# S05.net
KiCad netlist of a schematic drawn in Altium Designer
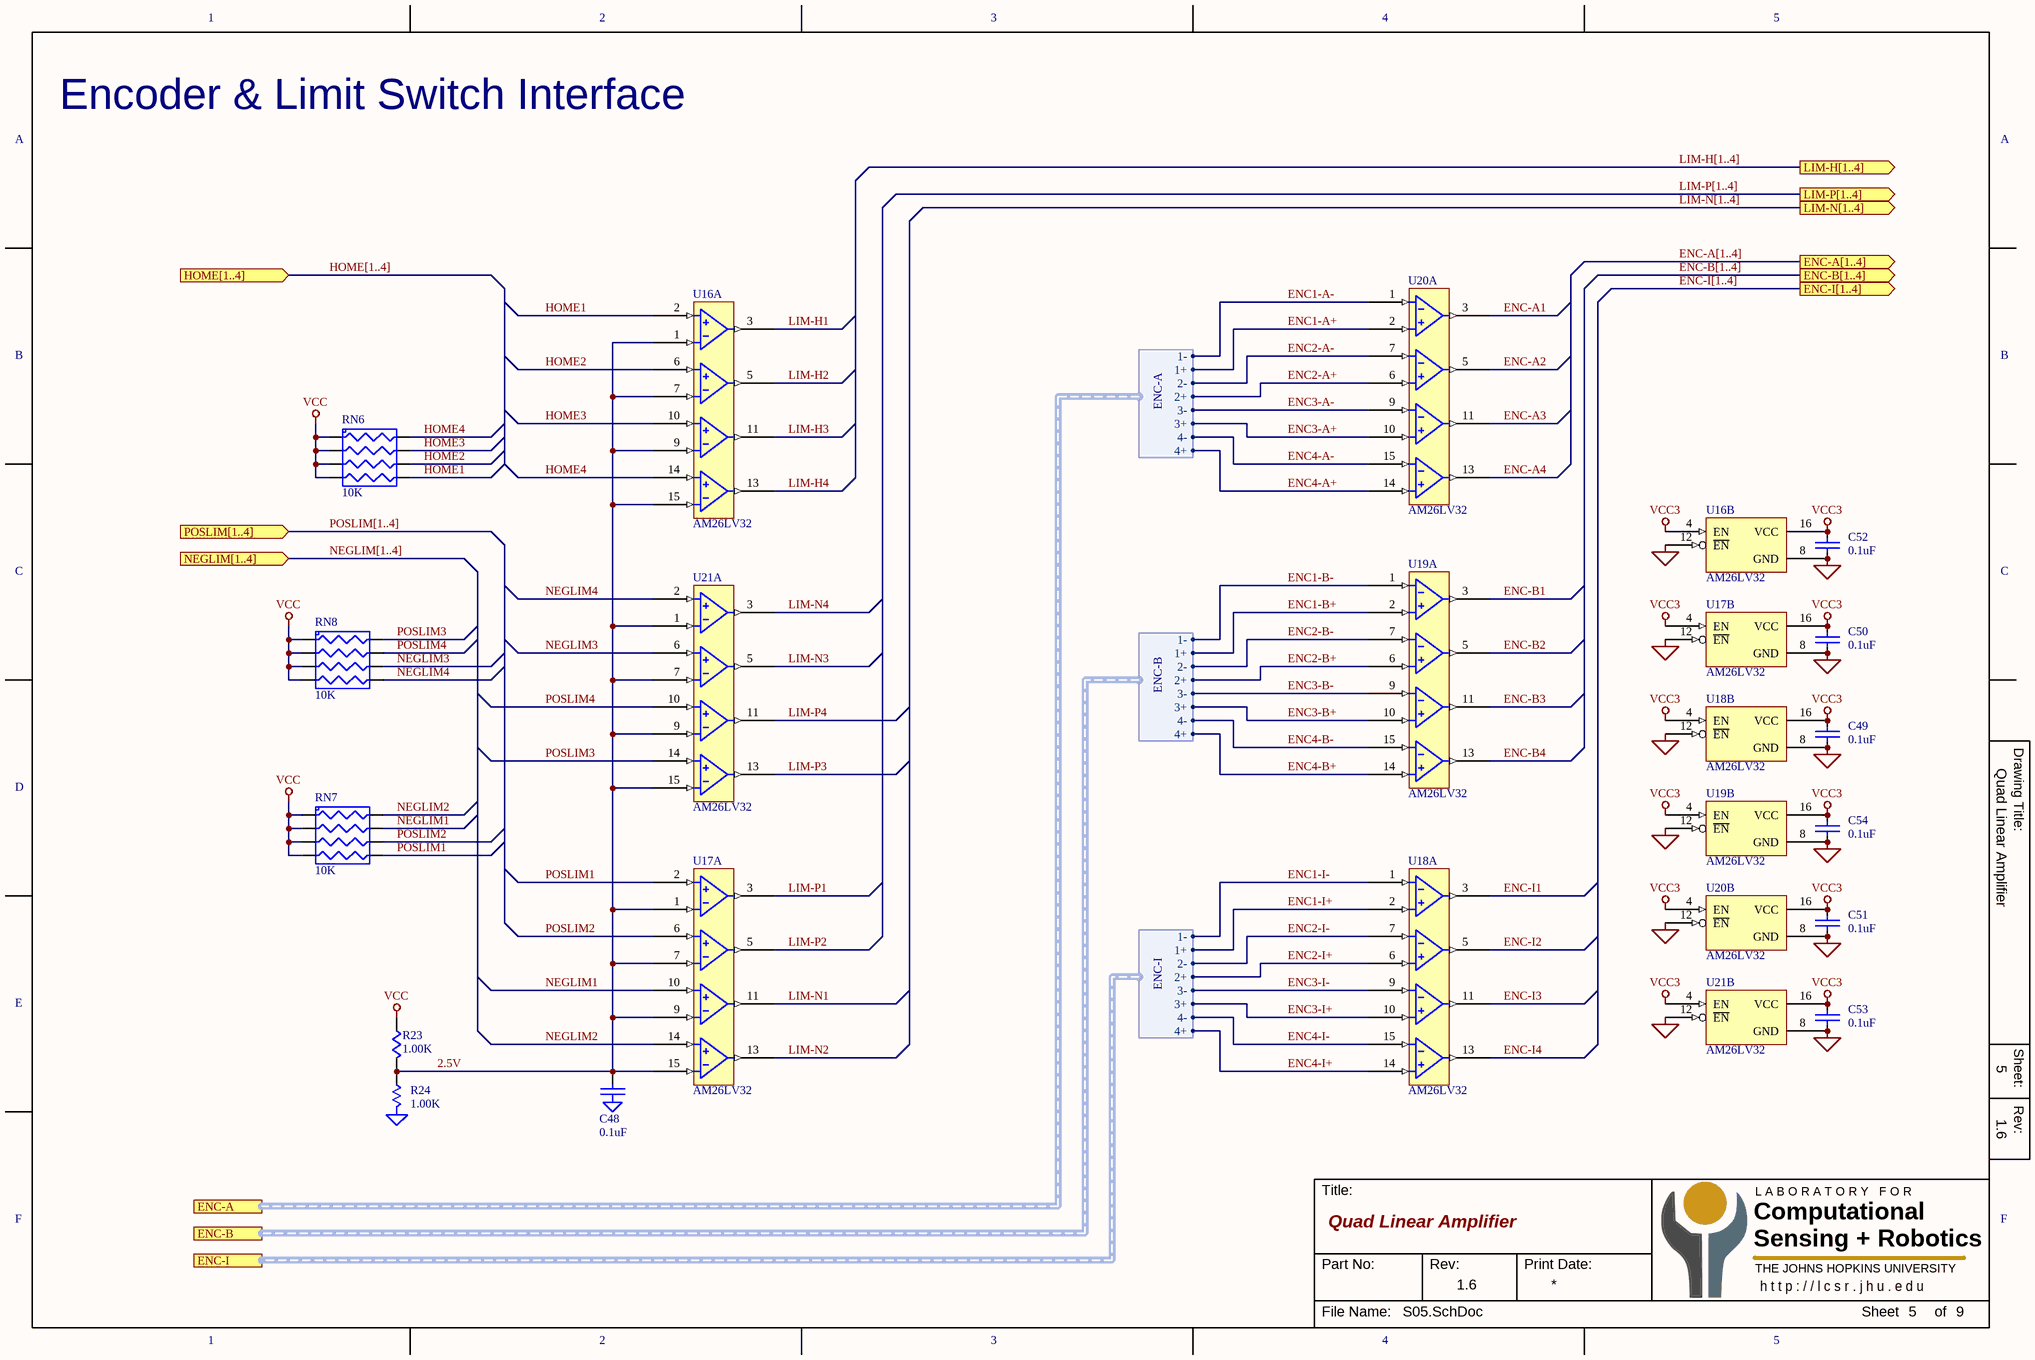
[diagram p0: S05.SchDoc]

(export (version "E")
  (design (tool "Eeschema 10.0.6"))
  (components
    (comp (ref "C48") (value "0.1uF") (footprint "C0603") (libsource (lib "QLA") (part "CAP-GND")))
    (comp (ref "C49") (value "0.1uF") (footprint "C0603") (libsource (lib "QLA") (part "CAP-MINI")))
    (comp (ref "C50") (value "0.1uF") (footprint "C0603") (libsource (lib "QLA") (part "CAP-MINI")))
    (comp (ref "C51") (value "0.1uF") (footprint "C0603") (libsource (lib "QLA") (part "CAP-MINI")))
    (comp (ref "C52") (value "0.1uF") (footprint "C0603") (libsource (lib "QLA") (part "CAP-MINI")))
    (comp (ref "C53") (value "0.1uF") (footprint "C0603") (libsource (lib "QLA") (part "CAP-MINI")))
    (comp (ref "C54") (value "0.1uF") (footprint "C0603") (libsource (lib "QLA") (part "CAP-MINI")))
    (comp (ref "R23") (value "1.00K") (footprint "R0603") (libsource (lib "QLA") (part "R")))
    (comp (ref "R24") (value "1.00K") (footprint "R0603") (libsource (lib "QLA") (part "R-GND")))
    (comp (ref "RN6") (value "10K") (footprint "RN-742C083") (libsource (lib "QLA") (part "RN-DISC-SM-4")))
    (comp (ref "RN7") (value "10K") (footprint "RN-742C083") (libsource (lib "QLA") (part "RN-DISC-SM-4")))
    (comp (ref "RN8") (value "10K") (footprint "RN-742C083") (libsource (lib "QLA") (part "RN-DISC-SM-4")))
    (comp (ref "U16") (value "AM26LV32") (footprint "SO-16") (libsource (lib "") (part "DS26LV32AT_1")))
    (comp (ref "U17") (value "AM26LV32") (footprint "SO-16") (libsource (lib "") (part "DS26LV32AT_1")))
    (comp (ref "U18") (value "AM26LV32") (footprint "SO-16") (libsource (lib "") (part "DS26LV32AT_1")))
    (comp (ref "U19") (value "AM26LV32") (footprint "SO-16") (libsource (lib "") (part "DS26LV32AT_1")))
    (comp (ref "U20") (value "AM26LV32") (footprint "SO-16") (libsource (lib "") (part "DS26LV32AT_1")))
    (comp (ref "U21") (value "AM26LV32") (footprint "SO-16") (libsource (lib "QLA") (part "DS26LV32AT")))
  )
  (nets
    (net (code "4") (name "/2.5V") (class "Default")
      (node (ref "C48") (pin "1") (pintype "passive"))
      (node (ref "R23") (pin "2") (pinfunction "2_2") (pintype "passive"))
      (node (ref "R24") (pin "1") (pinfunction "1_1") (pintype "passive"))
      (node (ref "U16") (pin "1") (pinfunction "A-_1") (pintype "input"))
      (node (ref "U16") (pin "15") (pinfunction "A-_15") (pintype "input"))
      (node (ref "U16") (pin "7") (pinfunction "A-_7") (pintype "input"))
      (node (ref "U16") (pin "9") (pinfunction "A-_9") (pintype "input"))
      (node (ref "U17") (pin "1") (pinfunction "A-_1") (pintype "input"))
      (node (ref "U17") (pin "15") (pinfunction "A-_15") (pintype "input"))
      (node (ref "U17") (pin "7") (pinfunction "A-_7") (pintype "input"))
      (node (ref "U17") (pin "9") (pinfunction "A-_9") (pintype "input"))
      (node (ref "U21") (pin "1") (pinfunction "A-_1") (pintype "input"))
      (node (ref "U21") (pin "15") (pinfunction "A-_15") (pintype "input"))
      (node (ref "U21") (pin "7") (pinfunction "A-_7") (pintype "input"))
      (node (ref "U21") (pin "9") (pinfunction "A-_9") (pintype "input"))
    )
    (net (code "5") (name "/ENC-A1") (class "Default")
      (node (ref "U20") (pin "3") (pinfunction "YA_3") (pintype "output"))
    )
    (net (code "6") (name "/ENC-A2") (class "Default")
      (node (ref "U20") (pin "5") (pinfunction "YA_5") (pintype "output"))
    )
    (net (code "7") (name "/ENC-A3") (class "Default")
      (node (ref "U20") (pin "11") (pinfunction "YA_11") (pintype "output"))
    )
    (net (code "8") (name "/ENC-A4") (class "Default")
      (node (ref "U20") (pin "13") (pinfunction "YA_13") (pintype "output"))
    )
    (net (code "10") (name "/ENC-B1") (class "Default")
      (node (ref "U19") (pin "3") (pinfunction "YA_3") (pintype "output"))
    )
    (net (code "11") (name "/ENC-B2") (class "Default")
      (node (ref "U19") (pin "5") (pinfunction "YA_5") (pintype "output"))
    )
    (net (code "12") (name "/ENC-B3") (class "Default")
      (node (ref "U19") (pin "11") (pinfunction "YA_11") (pintype "output"))
    )
    (net (code "13") (name "/ENC-B4") (class "Default")
      (node (ref "U19") (pin "13") (pinfunction "YA_13") (pintype "output"))
    )
    (net (code "15") (name "/ENC-I1") (class "Default")
      (node (ref "U18") (pin "3") (pinfunction "YA_3") (pintype "output"))
    )
    (net (code "16") (name "/ENC-I2") (class "Default")
      (node (ref "U18") (pin "5") (pinfunction "YA_5") (pintype "output"))
    )
    (net (code "17") (name "/ENC-I3") (class "Default")
      (node (ref "U18") (pin "11") (pinfunction "YA_11") (pintype "output"))
    )
    (net (code "18") (name "/ENC-I4") (class "Default")
      (node (ref "U18") (pin "13") (pinfunction "YA_13") (pintype "output"))
    )
    (net (code "20") (name "/ENC1-A+") (class "Default")
      (node (ref "U20") (pin "2") (pinfunction "A+_2") (pintype "input"))
    )
    (net (code "21") (name "/ENC1-A-") (class "Default")
      (node (ref "U20") (pin "1") (pinfunction "A-_1") (pintype "input"))
    )
    (net (code "22") (name "/ENC1-B+") (class "Default")
      (node (ref "U19") (pin "2") (pinfunction "A+_2") (pintype "input"))
    )
    (net (code "23") (name "/ENC1-B-") (class "Default")
      (node (ref "U19") (pin "1") (pinfunction "A-_1") (pintype "input"))
    )
    (net (code "24") (name "/ENC1-I+") (class "Default")
      (node (ref "U18") (pin "2") (pinfunction "A+_2") (pintype "input"))
    )
    (net (code "25") (name "/ENC1-I-") (class "Default")
      (node (ref "U18") (pin "1") (pinfunction "A-_1") (pintype "input"))
    )
    (net (code "26") (name "/ENC2-A+") (class "Default")
      (node (ref "U20") (pin "6") (pinfunction "A+_6") (pintype "input"))
    )
    (net (code "27") (name "/ENC2-A-") (class "Default")
      (node (ref "U20") (pin "7") (pinfunction "A-_7") (pintype "input"))
    )
    (net (code "28") (name "/ENC2-B+") (class "Default")
      (node (ref "U19") (pin "6") (pinfunction "A+_6") (pintype "input"))
    )
    (net (code "29") (name "/ENC2-B-") (class "Default")
      (node (ref "U19") (pin "7") (pinfunction "A-_7") (pintype "input"))
    )
    (net (code "30") (name "/ENC2-I+") (class "Default")
      (node (ref "U18") (pin "6") (pinfunction "A+_6") (pintype "input"))
    )
    (net (code "31") (name "/ENC2-I-") (class "Default")
      (node (ref "U18") (pin "7") (pinfunction "A-_7") (pintype "input"))
    )
    (net (code "32") (name "/ENC3-A+") (class "Default")
      (node (ref "U20") (pin "10") (pinfunction "A+_10") (pintype "input"))
    )
    (net (code "33") (name "/ENC3-A-") (class "Default")
      (node (ref "U20") (pin "9") (pinfunction "A-_9") (pintype "input"))
    )
    (net (code "34") (name "/ENC3-B+") (class "Default")
      (node (ref "U19") (pin "10") (pinfunction "A+_10") (pintype "input"))
    )
    (net (code "35") (name "/ENC3-B-") (class "Default")
      (node (ref "U19") (pin "9") (pinfunction "A-_9") (pintype "input"))
    )
    (net (code "36") (name "/ENC3-I+") (class "Default")
      (node (ref "U18") (pin "10") (pinfunction "A+_10") (pintype "input"))
    )
    (net (code "37") (name "/ENC3-I-") (class "Default")
      (node (ref "U18") (pin "9") (pinfunction "A-_9") (pintype "input"))
    )
    (net (code "38") (name "/ENC4-A+") (class "Default")
      (node (ref "U20") (pin "14") (pinfunction "A+_14") (pintype "input"))
    )
    (net (code "39") (name "/ENC4-A-") (class "Default")
      (node (ref "U20") (pin "15") (pinfunction "A-_15") (pintype "input"))
    )
    (net (code "40") (name "/ENC4-B+") (class "Default")
      (node (ref "U19") (pin "14") (pinfunction "A+_14") (pintype "input"))
    )
    (net (code "41") (name "/ENC4-B-") (class "Default")
      (node (ref "U19") (pin "15") (pinfunction "A-_15") (pintype "input"))
    )
    (net (code "42") (name "/ENC4-I+") (class "Default")
      (node (ref "U18") (pin "14") (pinfunction "A+_14") (pintype "input"))
    )
    (net (code "43") (name "/ENC4-I-") (class "Default")
      (node (ref "U18") (pin "15") (pinfunction "A-_15") (pintype "input"))
    )
    (net (code "44") (name "/HOME1") (class "Default")
      (node (ref "RN6") (pin "5") (pinfunction "R4.2_5") (pintype "passive"))
      (node (ref "U16") (pin "2") (pinfunction "A+_2") (pintype "input"))
    )
    (net (code "45") (name "/HOME2") (class "Default")
      (node (ref "RN6") (pin "6") (pinfunction "R3.2_6") (pintype "passive"))
      (node (ref "U16") (pin "6") (pinfunction "A+_6") (pintype "input"))
    )
    (net (code "46") (name "/HOME3") (class "Default")
      (node (ref "RN6") (pin "7") (pinfunction "R2.2_7") (pintype "passive"))
      (node (ref "U16") (pin "10") (pinfunction "A+_10") (pintype "input"))
    )
    (net (code "47") (name "/HOME4") (class "Default")
      (node (ref "RN6") (pin "8") (pinfunction "R1.2_8") (pintype "passive"))
      (node (ref "U16") (pin "14") (pinfunction "A+_14") (pintype "input"))
    )
    (net (code "49") (name "/LIM-H1") (class "Default")
      (node (ref "U16") (pin "3") (pinfunction "YA_3") (pintype "output"))
    )
    (net (code "50") (name "/LIM-H2") (class "Default")
      (node (ref "U16") (pin "5") (pinfunction "YA_5") (pintype "output"))
    )
    (net (code "51") (name "/LIM-H3") (class "Default")
      (node (ref "U16") (pin "11") (pinfunction "YA_11") (pintype "output"))
    )
    (net (code "52") (name "/LIM-H4") (class "Default")
      (node (ref "U16") (pin "13") (pinfunction "YA_13") (pintype "output"))
    )
    (net (code "54") (name "/LIM-N1") (class "Default")
      (node (ref "U17") (pin "11") (pinfunction "YA_11") (pintype "output"))
    )
    (net (code "55") (name "/LIM-N2") (class "Default")
      (node (ref "U17") (pin "13") (pinfunction "YA_13") (pintype "output"))
    )
    (net (code "56") (name "/LIM-N3") (class "Default")
      (node (ref "U21") (pin "5") (pinfunction "YA_5") (pintype "output"))
    )
    (net (code "57") (name "/LIM-N4") (class "Default")
      (node (ref "U21") (pin "3") (pinfunction "YA_3") (pintype "output"))
    )
    (net (code "59") (name "/LIM-P1") (class "Default")
      (node (ref "U17") (pin "3") (pinfunction "YA_3") (pintype "output"))
    )
    (net (code "60") (name "/LIM-P2") (class "Default")
      (node (ref "U17") (pin "5") (pinfunction "YA_5") (pintype "output"))
    )
    (net (code "61") (name "/LIM-P3") (class "Default")
      (node (ref "U21") (pin "13") (pinfunction "YA_13") (pintype "output"))
    )
    (net (code "62") (name "/LIM-P4") (class "Default")
      (node (ref "U21") (pin "11") (pinfunction "YA_11") (pintype "output"))
    )
    (net (code "64") (name "/NEGLIM1") (class "Default")
      (node (ref "RN7") (pin "7") (pinfunction "R2.2_7") (pintype "passive"))
      (node (ref "U17") (pin "10") (pinfunction "A+_10") (pintype "input"))
    )
    (net (code "65") (name "/NEGLIM2") (class "Default")
      (node (ref "RN7") (pin "8") (pinfunction "R1.2_8") (pintype "passive"))
      (node (ref "U17") (pin "14") (pinfunction "A+_14") (pintype "input"))
    )
    (net (code "66") (name "/NEGLIM3") (class "Default")
      (node (ref "RN8") (pin "6") (pinfunction "R3.2_6") (pintype "passive"))
      (node (ref "U21") (pin "6") (pinfunction "A+_6") (pintype "input"))
    )
    (net (code "67") (name "/NEGLIM4") (class "Default")
      (node (ref "RN8") (pin "5") (pinfunction "R4.2_5") (pintype "passive"))
      (node (ref "U21") (pin "2") (pinfunction "A+_2") (pintype "input"))
    )
    (net (code "69") (name "/POSLIM1") (class "Default")
      (node (ref "RN7") (pin "5") (pinfunction "R4.2_5") (pintype "passive"))
      (node (ref "U17") (pin "2") (pinfunction "A+_2") (pintype "input"))
    )
    (net (code "70") (name "/POSLIM2") (class "Default")
      (node (ref "RN7") (pin "6") (pinfunction "R3.2_6") (pintype "passive"))
      (node (ref "U17") (pin "6") (pinfunction "A+_6") (pintype "input"))
    )
    (net (code "71") (name "/POSLIM3") (class "Default")
      (node (ref "RN8") (pin "8") (pinfunction "R1.2_8") (pintype "passive"))
      (node (ref "U21") (pin "14") (pinfunction "A+_14") (pintype "input"))
    )
    (net (code "72") (name "/POSLIM4") (class "Default")
      (node (ref "RN8") (pin "7") (pinfunction "R2.2_7") (pintype "passive"))
      (node (ref "U21") (pin "10") (pinfunction "A+_10") (pintype "input"))
    )
    (net (code "77") (name "GND") (class "Default")
      (node (ref "C48") (pin "2") (pinfunction "GND_2") (pintype "power_in"))
      (node (ref "C49") (pin "2") (pintype "passive"))
      (node (ref "C50") (pin "2") (pintype "passive"))
      (node (ref "C51") (pin "2") (pintype "passive"))
      (node (ref "C52") (pin "2") (pintype "passive"))
      (node (ref "C53") (pin "2") (pintype "passive"))
      (node (ref "C54") (pin "2") (pintype "passive"))
      (node (ref "R24") (pin "2") (pinfunction "GND_2") (pintype "power_in"))
      (node (ref "U16") (pin "12") (pinfunction "EN_12") (pintype "input"))
      (node (ref "U16") (pin "8") (pinfunction "GND_8") (pintype "power_in"))
      (node (ref "U17") (pin "12") (pinfunction "EN_12") (pintype "input"))
      (node (ref "U17") (pin "8") (pinfunction "GND_8") (pintype "power_in"))
      (node (ref "U18") (pin "12") (pinfunction "EN_12") (pintype "input"))
      (node (ref "U18") (pin "8") (pinfunction "GND_8") (pintype "power_in"))
      (node (ref "U19") (pin "12") (pinfunction "EN_12") (pintype "input"))
      (node (ref "U19") (pin "8") (pinfunction "GND_8") (pintype "power_in"))
      (node (ref "U20") (pin "12") (pinfunction "EN_12") (pintype "input"))
      (node (ref "U20") (pin "8") (pinfunction "GND_8") (pintype "power_in"))
      (node (ref "U21") (pin "12") (pinfunction "EN_12") (pintype "input"))
      (node (ref "U21") (pin "8") (pinfunction "GND_8") (pintype "power_in"))
    )
    (net (code "78") (name "VCC") (class "Default")
      (node (ref "R23") (pin "1") (pinfunction "1_1") (pintype "passive"))
      (node (ref "RN6") (pin "1") (pinfunction "R1_1") (pintype "passive"))
      (node (ref "RN6") (pin "2") (pinfunction "R2.1_2") (pintype "passive"))
      (node (ref "RN6") (pin "3") (pinfunction "R3.1_3") (pintype "passive"))
      (node (ref "RN6") (pin "4") (pinfunction "R4.1_4") (pintype "passive"))
      (node (ref "RN7") (pin "1") (pinfunction "R1_1") (pintype "passive"))
      (node (ref "RN7") (pin "2") (pinfunction "R2.1_2") (pintype "passive"))
      (node (ref "RN7") (pin "3") (pinfunction "R3.1_3") (pintype "passive"))
      (node (ref "RN7") (pin "4") (pinfunction "R4.1_4") (pintype "passive"))
      (node (ref "RN8") (pin "1") (pinfunction "R1_1") (pintype "passive"))
      (node (ref "RN8") (pin "2") (pinfunction "R2.1_2") (pintype "passive"))
      (node (ref "RN8") (pin "3") (pinfunction "R3.1_3") (pintype "passive"))
      (node (ref "RN8") (pin "4") (pinfunction "R4.1_4") (pintype "passive"))
    )
    (net (code "79") (name "VCC3") (class "Default")
      (node (ref "C49") (pin "1") (pintype "passive"))
      (node (ref "C50") (pin "1") (pintype "passive"))
      (node (ref "C51") (pin "1") (pintype "passive"))
      (node (ref "C52") (pin "1") (pintype "passive"))
      (node (ref "C53") (pin "1") (pintype "passive"))
      (node (ref "C54") (pin "1") (pintype "passive"))
      (node (ref "U16") (pin "16") (pinfunction "VCC_16") (pintype "power_in"))
      (node (ref "U16") (pin "4") (pinfunction "EN_4") (pintype "input"))
      (node (ref "U17") (pin "16") (pinfunction "VCC_16") (pintype "power_in"))
      (node (ref "U17") (pin "4") (pinfunction "EN_4") (pintype "input"))
      (node (ref "U18") (pin "16") (pinfunction "VCC_16") (pintype "power_in"))
      (node (ref "U18") (pin "4") (pinfunction "EN_4") (pintype "input"))
      (node (ref "U19") (pin "16") (pinfunction "VCC_16") (pintype "power_in"))
      (node (ref "U19") (pin "4") (pinfunction "EN_4") (pintype "input"))
      (node (ref "U20") (pin "16") (pinfunction "VCC_16") (pintype "power_in"))
      (node (ref "U20") (pin "4") (pinfunction "EN_4") (pintype "input"))
      (node (ref "U21") (pin "16") (pinfunction "VCC_16") (pintype "power_in"))
      (node (ref "U21") (pin "4") (pinfunction "EN_4") (pintype "input"))
    )
  )
)
